# EMI_Detect_V1_1.net
KiCad netlist of a schematic drawn in EAGLE
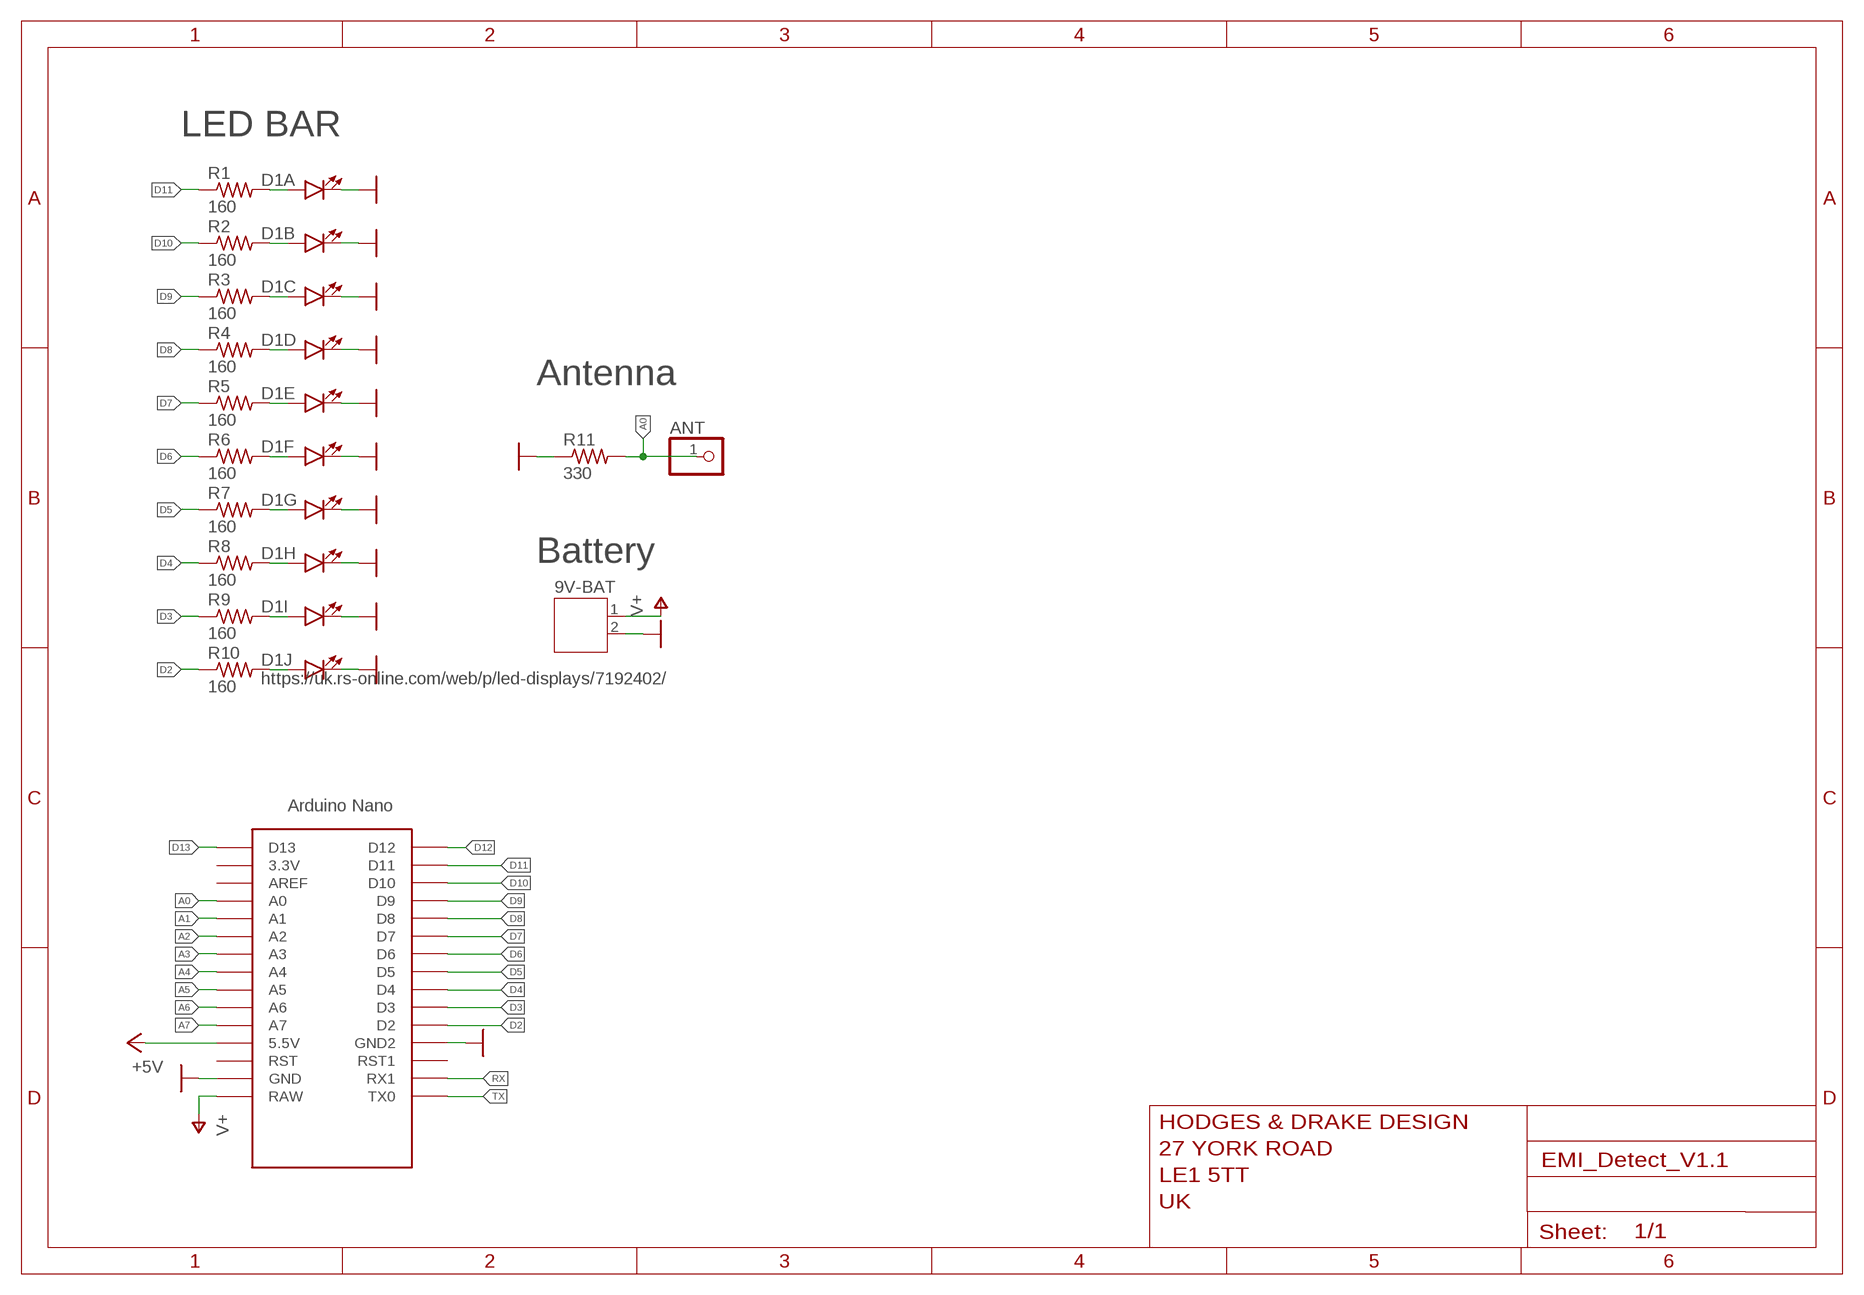
[diagram p0: schematic, sheet 1]

(export (version "E")
  (design (tool "Eeschema 10.0.6"))
  (components
    (comp (ref "9V-BAT")
      (value "JST-PH2")
      (footprint "eagle-import:JST-PH2-S2B")
      (libsource (lib "eagle-import") (part "JST-PH2"))
    )
    (comp (ref "ANT")
      (value "PINHD-1X1")
      (footprint "eagle-import:1X01")
      (libsource (lib "eagle-import") (part "PINHD-1X1"))
    )
    (comp (ref "D1")
      (value "https://uk.rs-online.com/web/p/led-displays/7192402/")
      (footprint "eagle-import:LED_BARGAPH_10")
      (libsource (lib "eagle-import") (part "LED_BARGRAPH_10"))
    )
    (comp (ref "R1")
      (value "160")
      (footprint "eagle-import:R0603")
      (libsource (lib "eagle-import") (part "R-US_R0603"))
    )
    (comp (ref "R2")
      (value "160")
      (footprint "eagle-import:R0603")
      (libsource (lib "eagle-import") (part "R-US_R0603"))
    )
    (comp (ref "R3")
      (value "160")
      (footprint "eagle-import:R0603")
      (libsource (lib "eagle-import") (part "R-US_R0603"))
    )
    (comp (ref "R4")
      (value "160")
      (footprint "eagle-import:R0603")
      (libsource (lib "eagle-import") (part "R-US_R0603"))
    )
    (comp (ref "R5")
      (value "160")
      (footprint "eagle-import:R0603")
      (libsource (lib "eagle-import") (part "R-US_R0603"))
    )
    (comp (ref "R6")
      (value "160")
      (footprint "eagle-import:R0603")
      (libsource (lib "eagle-import") (part "R-US_R0603"))
    )
    (comp (ref "R7")
      (value "160")
      (footprint "eagle-import:R0603")
      (libsource (lib "eagle-import") (part "R-US_R0603"))
    )
    (comp (ref "R8")
      (value "160")
      (footprint "eagle-import:R0603")
      (libsource (lib "eagle-import") (part "R-US_R0603"))
    )
    (comp (ref "R9")
      (value "160")
      (footprint "eagle-import:R0603")
      (libsource (lib "eagle-import") (part "R-US_R0603"))
    )
    (comp (ref "R10")
      (value "160")
      (footprint "eagle-import:R0603")
      (libsource (lib "eagle-import") (part "R-US_R0603"))
    )
    (comp (ref "R11")
      (value "330")
      (footprint "eagle-import:R0603")
      (libsource (lib "eagle-import") (part "R-US_R0603"))
    )
    (comp (ref "U1")
      (value "NANO")
      (footprint "eagle-import:NANO")
      (libsource (lib "eagle-import") (part "NANO"))
    )
  )
  (nets
    (net (code "1") (name "+5V") (class "Default")
      (node (ref "U1") (pin "5V") (pinfunction "5.5V_5V") (pintype "bidirectional"))
    )
    (net (code "2") (name "A0") (class "Default")
      (node (ref "ANT") (pin "1") (pinfunction "1_1") (pintype "passive"))
      (node (ref "R11") (pin "2") (pinfunction "2_2") (pintype "passive"))
      (node (ref "U1") (pin "A0") (pinfunction "A0_A0") (pintype "bidirectional"))
    )
    (net (code "3") (name "A1") (class "Default")
      (node (ref "U1") (pin "A1") (pinfunction "A1_A1") (pintype "bidirectional"))
    )
    (net (code "4") (name "A2") (class "Default")
      (node (ref "U1") (pin "A2") (pinfunction "A2_A2") (pintype "bidirectional"))
    )
    (net (code "5") (name "A3") (class "Default")
      (node (ref "U1") (pin "A3") (pinfunction "A3_A3") (pintype "bidirectional"))
    )
    (net (code "6") (name "A4") (class "Default")
      (node (ref "U1") (pin "A4") (pinfunction "A4_A4") (pintype "bidirectional"))
    )
    (net (code "7") (name "A5") (class "Default")
      (node (ref "U1") (pin "A5") (pinfunction "A5_A5") (pintype "bidirectional"))
    )
    (net (code "8") (name "A6") (class "Default")
      (node (ref "U1") (pin "A6") (pinfunction "A6_A6") (pintype "bidirectional"))
    )
    (net (code "9") (name "A7") (class "Default")
      (node (ref "U1") (pin "A7") (pinfunction "A7_A7") (pintype "bidirectional"))
    )
    (net (code "10") (name "D2") (class "Default")
      (node (ref "R10") (pin "1") (pinfunction "1_1") (pintype "passive"))
      (node (ref "U1") (pin "D2") (pinfunction "D2_D2") (pintype "bidirectional"))
    )
    (net (code "11") (name "D3") (class "Default")
      (node (ref "R9") (pin "1") (pinfunction "1_1") (pintype "passive"))
      (node (ref "U1") (pin "D3") (pinfunction "D3_D3") (pintype "bidirectional"))
    )
    (net (code "12") (name "D4") (class "Default")
      (node (ref "R8") (pin "1") (pinfunction "1_1") (pintype "passive"))
      (node (ref "U1") (pin "D4") (pinfunction "D4_D4") (pintype "bidirectional"))
    )
    (net (code "13") (name "D5") (class "Default")
      (node (ref "R7") (pin "1") (pinfunction "1_1") (pintype "passive"))
      (node (ref "U1") (pin "D5") (pinfunction "D5_D5") (pintype "bidirectional"))
    )
    (net (code "14") (name "D6") (class "Default")
      (node (ref "R6") (pin "1") (pinfunction "1_1") (pintype "passive"))
      (node (ref "U1") (pin "D6") (pinfunction "D6_D6") (pintype "bidirectional"))
    )
    (net (code "15") (name "D7") (class "Default")
      (node (ref "R5") (pin "1") (pinfunction "1_1") (pintype "passive"))
      (node (ref "U1") (pin "D7") (pinfunction "D7_D7") (pintype "bidirectional"))
    )
    (net (code "16") (name "D8") (class "Default")
      (node (ref "R4") (pin "1") (pinfunction "1_1") (pintype "passive"))
      (node (ref "U1") (pin "D8") (pinfunction "D8_D8") (pintype "bidirectional"))
    )
    (net (code "17") (name "D9") (class "Default")
      (node (ref "R3") (pin "1") (pinfunction "1_1") (pintype "passive"))
      (node (ref "U1") (pin "D9") (pinfunction "D9_D9") (pintype "bidirectional"))
    )
    (net (code "18") (name "D10") (class "Default")
      (node (ref "R2") (pin "1") (pinfunction "1_1") (pintype "passive"))
      (node (ref "U1") (pin "D10") (pinfunction "D10_D10") (pintype "bidirectional"))
    )
    (net (code "19") (name "D11") (class "Default")
      (node (ref "R1") (pin "1") (pinfunction "1_1") (pintype "passive"))
      (node (ref "U1") (pin "D11") (pinfunction "D11_D11") (pintype "bidirectional"))
    )
    (net (code "20") (name "D12") (class "Default")
      (node (ref "U1") (pin "D12") (pinfunction "D12_D12") (pintype "bidirectional"))
    )
    (net (code "21") (name "D13") (class "Default")
      (node (ref "U1") (pin "D13") (pinfunction "D13_D13") (pintype "bidirectional"))
    )
    (net (code "22") (name "GND") (class "Default")
      (node (ref "9V-BAT") (pin "2") (pinfunction "2_2") (pintype "passive"))
      (node (ref "D1") (pin "11") (pinfunction "C_11") (pintype "passive"))
      (node (ref "D1") (pin "12") (pinfunction "C_12") (pintype "passive"))
      (node (ref "D1") (pin "13") (pinfunction "C_13") (pintype "passive"))
      (node (ref "D1") (pin "14") (pinfunction "C_14") (pintype "passive"))
      (node (ref "D1") (pin "15") (pinfunction "C_15") (pintype "passive"))
      (node (ref "D1") (pin "16") (pinfunction "C_16") (pintype "passive"))
      (node (ref "D1") (pin "17") (pinfunction "C_17") (pintype "passive"))
      (node (ref "D1") (pin "18") (pinfunction "C_18") (pintype "passive"))
      (node (ref "D1") (pin "19") (pinfunction "C_19") (pintype "passive"))
      (node (ref "D1") (pin "20") (pinfunction "C_20") (pintype "passive"))
      (node (ref "R11") (pin "1") (pinfunction "1_1") (pintype "passive"))
      (node (ref "U1") (pin "GND") (pinfunction "GND_GND") (pintype "bidirectional"))
      (node (ref "U1") (pin "GND1") (pinfunction "GND2_GND1") (pintype "bidirectional"))
    )
    (net (code "23") (name "Net-(D1A-A)") (class "Default")
      (node (ref "D1") (pin "1") (pinfunction "A_1") (pintype "passive"))
      (node (ref "R1") (pin "2") (pinfunction "2_2") (pintype "passive"))
    )
    (net (code "24") (name "Net-(D1B-A)") (class "Default")
      (node (ref "D1") (pin "2") (pinfunction "A_2") (pintype "passive"))
      (node (ref "R2") (pin "2") (pinfunction "2_2") (pintype "passive"))
    )
    (net (code "25") (name "Net-(D1C-A)") (class "Default")
      (node (ref "D1") (pin "3") (pinfunction "A_3") (pintype "passive"))
      (node (ref "R3") (pin "2") (pinfunction "2_2") (pintype "passive"))
    )
    (net (code "26") (name "Net-(D1D-A)") (class "Default")
      (node (ref "D1") (pin "4") (pinfunction "A_4") (pintype "passive"))
      (node (ref "R4") (pin "2") (pinfunction "2_2") (pintype "passive"))
    )
    (net (code "27") (name "Net-(D1E-A)") (class "Default")
      (node (ref "D1") (pin "5") (pinfunction "A_5") (pintype "passive"))
      (node (ref "R5") (pin "2") (pinfunction "2_2") (pintype "passive"))
    )
    (net (code "28") (name "Net-(D1F-A)") (class "Default")
      (node (ref "D1") (pin "6") (pinfunction "A_6") (pintype "passive"))
      (node (ref "R6") (pin "2") (pinfunction "2_2") (pintype "passive"))
    )
    (net (code "29") (name "Net-(D1G-A)") (class "Default")
      (node (ref "D1") (pin "7") (pinfunction "A_7") (pintype "passive"))
      (node (ref "R7") (pin "2") (pinfunction "2_2") (pintype "passive"))
    )
    (net (code "30") (name "Net-(D1H-A)") (class "Default")
      (node (ref "D1") (pin "8") (pinfunction "A_8") (pintype "passive"))
      (node (ref "R8") (pin "2") (pinfunction "2_2") (pintype "passive"))
    )
    (net (code "31") (name "Net-(D1I-A)") (class "Default")
      (node (ref "D1") (pin "9") (pinfunction "A_9") (pintype "passive"))
      (node (ref "R9") (pin "2") (pinfunction "2_2") (pintype "passive"))
    )
    (net (code "32") (name "Net-(D1J-A)") (class "Default")
      (node (ref "D1") (pin "10") (pinfunction "A_10") (pintype "passive"))
      (node (ref "R10") (pin "2") (pinfunction "2_2") (pintype "passive"))
    )
    (net (code "33") (name "RX") (class "Default")
      (node (ref "U1") (pin "RX1") (pinfunction "RX1_RX1") (pintype "bidirectional"))
    )
    (net (code "34") (name "TX") (class "Default")
      (node (ref "U1") (pin "TX0") (pinfunction "TX0_TX0") (pintype "bidirectional"))
    )
    (net (code "35") (name "V+") (class "Default")
      (node (ref "9V-BAT") (pin "1") (pinfunction "1_1") (pintype "passive"))
      (node (ref "U1") (pin "RAW") (pinfunction "RAW_RAW") (pintype "bidirectional"))
    )
    (net (code "36") (name "unconnected-(U1-Pad3.3V)") (class "Default")
      (node (ref "U1") (pin "3.3V") (pinfunction "3.3V_3.3V") (pintype "bidirectional"))
    )
    (net (code "37") (name "unconnected-(U1-PadAREF)") (class "Default")
      (node (ref "U1") (pin "AREF") (pinfunction "AREF_AREF") (pintype "bidirectional"))
    )
    (net (code "38") (name "unconnected-(U1-PadICSP1)") (class "Default")
      (node (ref "U1") (pin "ICSP1") (pinfunction "ICSP1_ICSP1") (pintype "bidirectional"))
    )
    (net (code "39") (name "unconnected-(U1-PadICSP2)") (class "Default")
      (node (ref "U1") (pin "ICSP2") (pinfunction "ICSP2_ICSP2") (pintype "bidirectional"))
    )
    (net (code "40") (name "unconnected-(U1-PadICSP3)") (class "Default")
      (node (ref "U1") (pin "ICSP3") (pinfunction "ICSP3_ICSP3") (pintype "bidirectional"))
    )
    (net (code "41") (name "unconnected-(U1-PadICSP4)") (class "Default")
      (node (ref "U1") (pin "ICSP4") (pinfunction "ICSP4_ICSP4") (pintype "bidirectional"))
    )
    (net (code "42") (name "unconnected-(U1-PadICSP5)") (class "Default")
      (node (ref "U1") (pin "ICSP5") (pinfunction "ICSP5_ICSP5") (pintype "bidirectional"))
    )
    (net (code "43") (name "unconnected-(U1-PadICSP6)") (class "Default")
      (node (ref "U1") (pin "ICSP6") (pinfunction "ICSP6_ICSP6") (pintype "bidirectional"))
    )
    (net (code "44") (name "unconnected-(U1-PadRST)") (class "Default")
      (node (ref "U1") (pin "RST") (pinfunction "RST_RST") (pintype "bidirectional"))
    )
    (net (code "45") (name "unconnected-(U1-PadRST1)") (class "Default")
      (node (ref "U1") (pin "RST1") (pinfunction "RST1_RST1") (pintype "bidirectional"))
    )
  )
)
